# LD_driver.net
KiCad netlist of a schematic drawn in Altium Designer
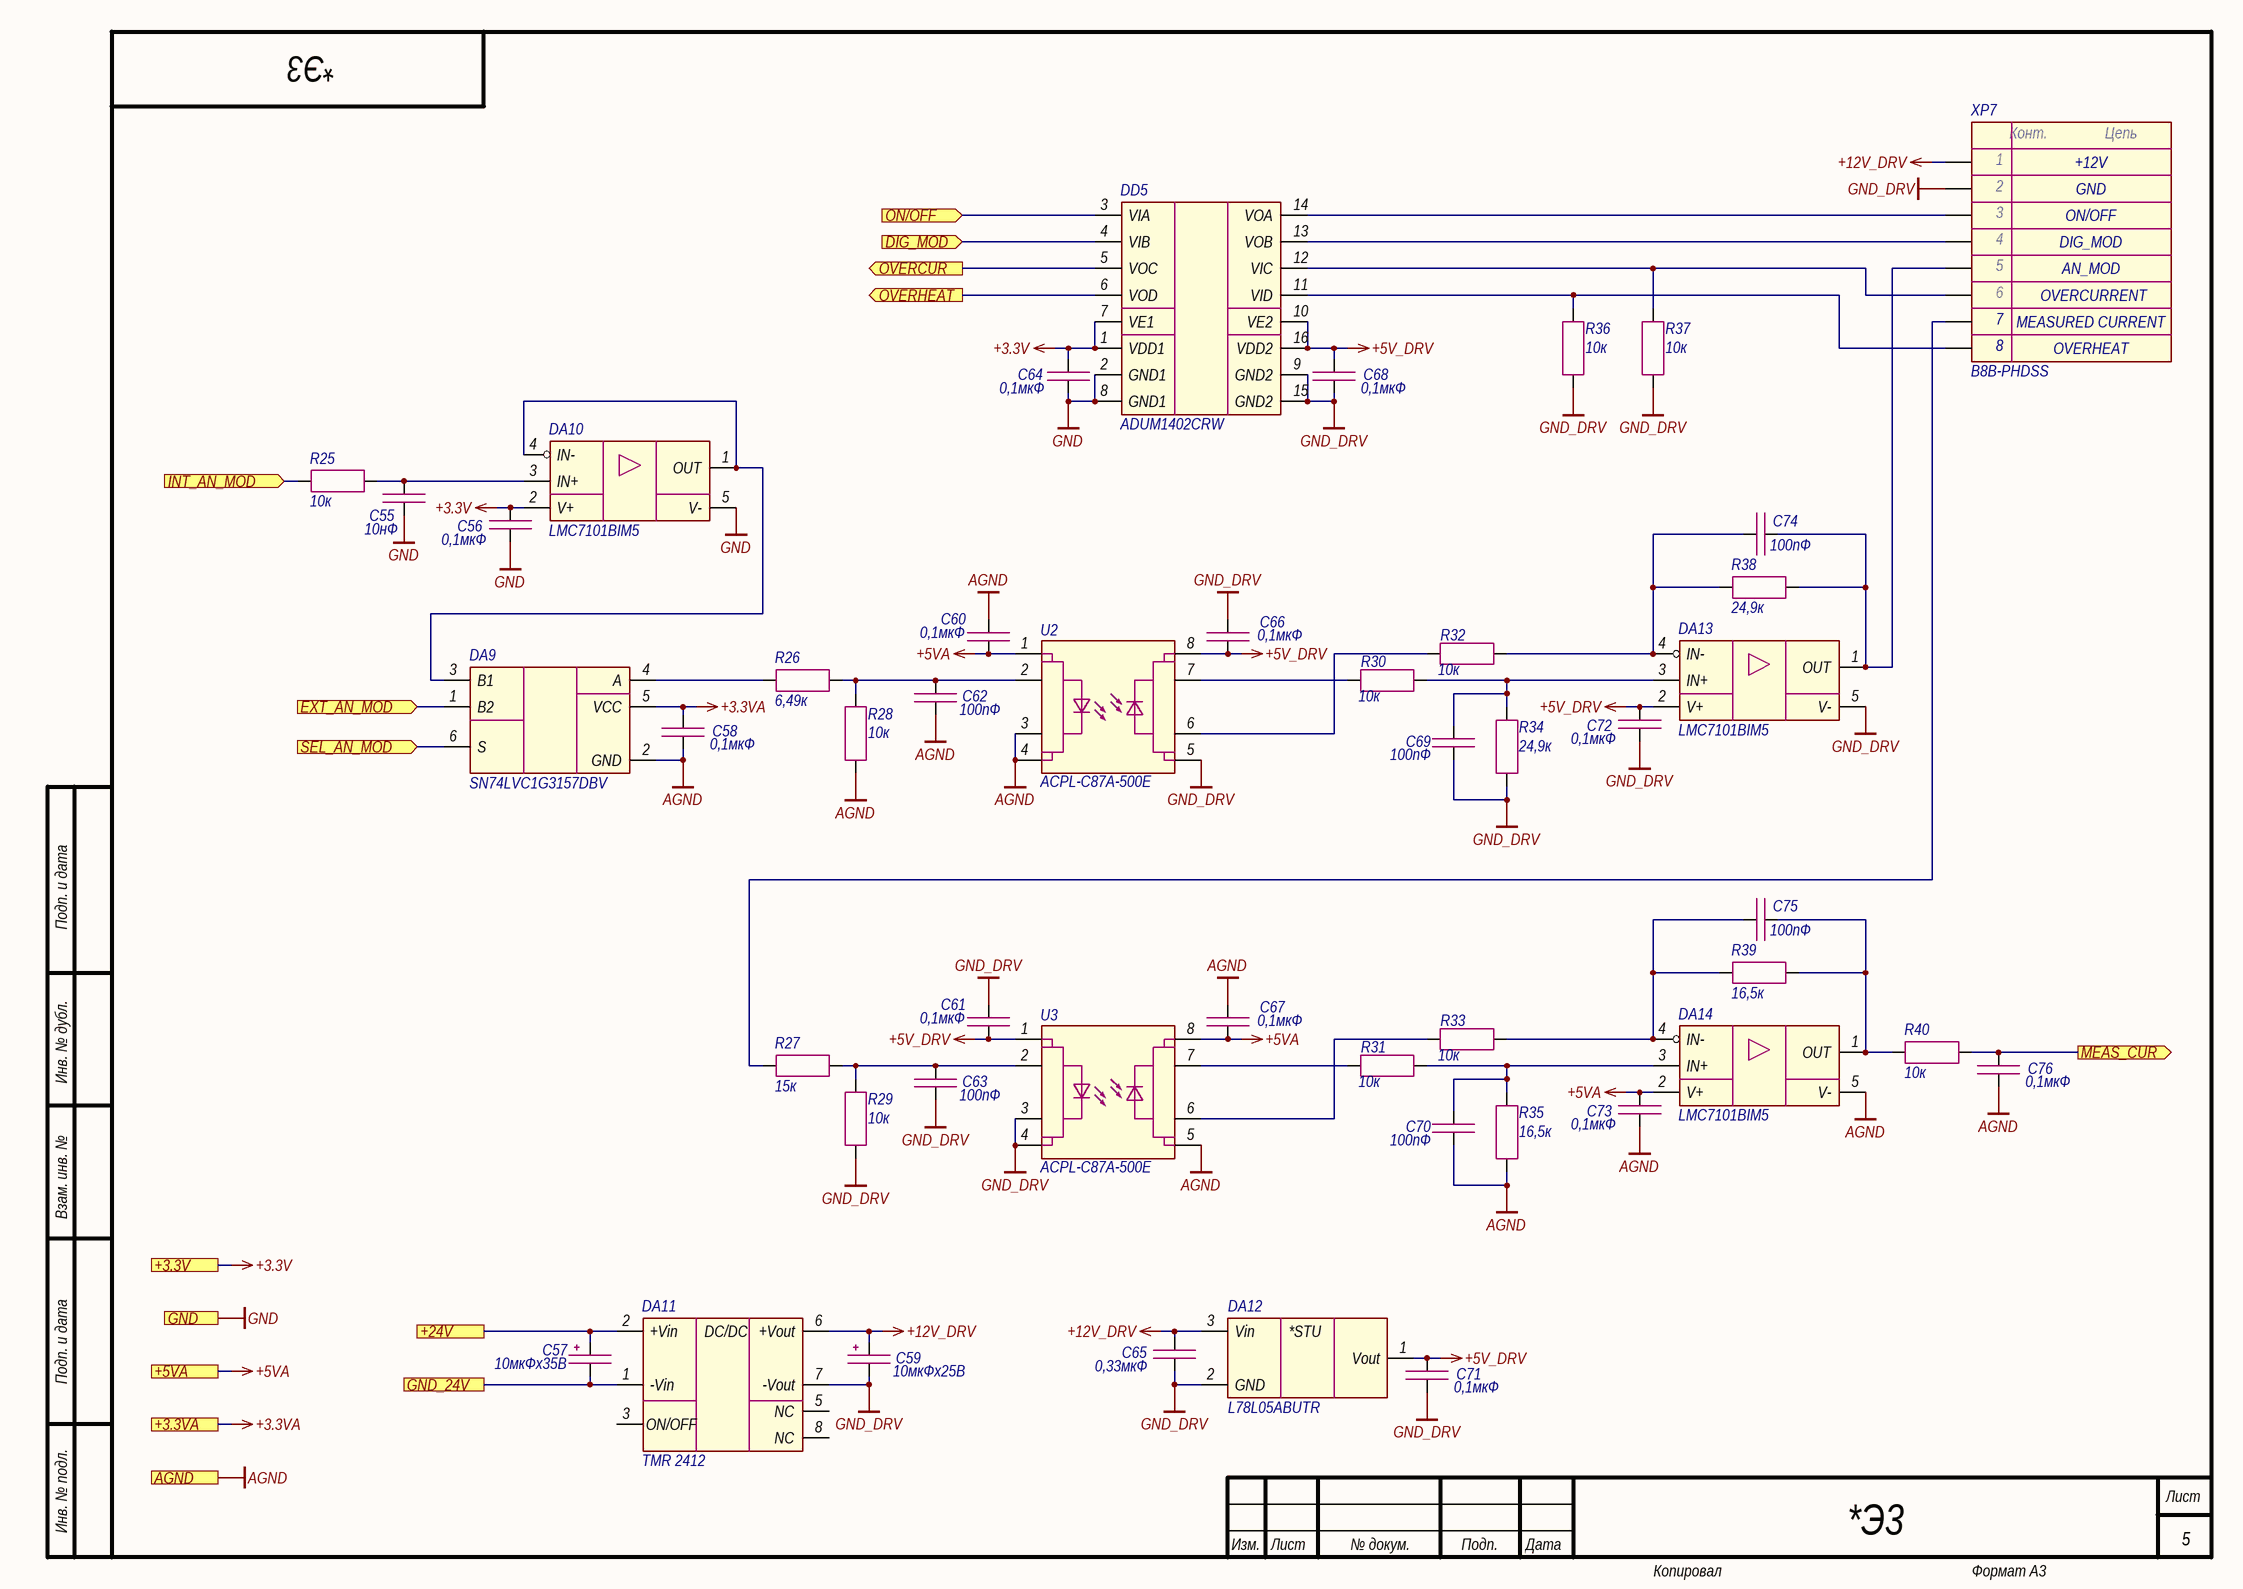
[diagram p0: LD_driver.SchDoc]

(export (version "E")
  (design (tool "Eeschema 10.0.6"))
  (components
    (comp (ref "C55")
      (value "10нФ")
      (footprint "Pcb_library:CAP_0603")
      (fields (field (name "MANUFACTURER") "Murata"))
      (libsource (lib "Schem_library") (part "Capacitor"))
    )
    (comp (ref "C56")
      (value "0,1мкФ")
      (footprint "Pcb_library:CAP_0603")
      (fields (field (name "MANUFACTURER") "Murata"))
      (libsource (lib "Schem_library") (part "Capacitor"))
    )
    (comp (ref "C57")
      (value "10мкФх35B")
      (footprint "Pcb_library:CAP_C")
      (libsource (lib "Schem_library") (part "Capacitor_Polar"))
    )
    (comp (ref "C58")
      (value "0,1мкФ")
      (footprint "Pcb_library:CAP_0603")
      (fields (field (name "MANUFACTURER") "Murata"))
      (libsource (lib "Schem_library") (part "Capacitor"))
    )
    (comp (ref "C59")
      (value "10мкФх25B")
      (footprint "Pcb_library:CAP_B")
      (libsource (lib "Schem_library") (part "Capacitor_Polar"))
    )
    (comp (ref "C60")
      (value "0,1мкФ")
      (footprint "Pcb_library:CAP_0603")
      (fields (field (name "MANUFACTURER") "Murata"))
      (libsource (lib "Schem_library") (part "Capacitor"))
    )
    (comp (ref "C61")
      (value "0,1мкФ")
      (footprint "Pcb_library:CAP_0603")
      (fields (field (name "MANUFACTURER") "Murata"))
      (libsource (lib "Schem_library") (part "Capacitor"))
    )
    (comp (ref "C62")
      (value "100пФ")
      (footprint "Pcb_library:CAP_0603")
      (fields (field (name "MANUFACTURER") "Murata"))
      (libsource (lib "Schem_library") (part "Capacitor"))
    )
    (comp (ref "C63")
      (value "100пФ")
      (footprint "Pcb_library:CAP_0603")
      (fields (field (name "MANUFACTURER") "Murata"))
      (libsource (lib "Schem_library") (part "Capacitor"))
    )
    (comp (ref "C64")
      (value "0,1мкФ")
      (footprint "Pcb_library:CAP_0603")
      (fields (field (name "MANUFACTURER") "Murata"))
      (libsource (lib "Schem_library") (part "Capacitor"))
    )
    (comp (ref "C65")
      (value "0,33мкФ")
      (footprint "Pcb_library:CAP_0805")
      (fields (field (name "MANUFACTURER") "Murata"))
      (libsource (lib "Schem_library") (part "Capacitor"))
    )
    (comp (ref "C66")
      (value "0,1мкФ")
      (footprint "Pcb_library:CAP_0603")
      (fields (field (name "MANUFACTURER") "Murata"))
      (libsource (lib "Schem_library") (part "Capacitor"))
    )
    (comp (ref "C67")
      (value "0,1мкФ")
      (footprint "Pcb_library:CAP_0603")
      (fields (field (name "MANUFACTURER") "Murata"))
      (libsource (lib "Schem_library") (part "Capacitor"))
    )
    (comp (ref "C68")
      (value "0,1мкФ")
      (footprint "Pcb_library:CAP_0603")
      (fields (field (name "MANUFACTURER") "Murata"))
      (libsource (lib "Schem_library") (part "Capacitor"))
    )
    (comp (ref "C69")
      (value "100пФ")
      (footprint "Pcb_library:CAP_0603")
      (fields (field (name "MANUFACTURER") "Murata"))
      (libsource (lib "Schem_library") (part "Capacitor"))
    )
    (comp (ref "C70")
      (value "100пФ")
      (footprint "Pcb_library:CAP_0603")
      (fields (field (name "MANUFACTURER") "Murata"))
      (libsource (lib "Schem_library") (part "Capacitor"))
    )
    (comp (ref "C71")
      (value "0,1мкФ")
      (footprint "Pcb_library:CAP_0603")
      (fields (field (name "MANUFACTURER") "Murata"))
      (libsource (lib "Schem_library") (part "Capacitor"))
    )
    (comp (ref "C72")
      (value "0,1мкФ")
      (footprint "Pcb_library:CAP_0603")
      (fields (field (name "MANUFACTURER") "Murata"))
      (libsource (lib "Schem_library") (part "Capacitor"))
    )
    (comp (ref "C73")
      (value "0,1мкФ")
      (footprint "Pcb_library:CAP_0603")
      (fields (field (name "MANUFACTURER") "Murata"))
      (libsource (lib "Schem_library") (part "Capacitor"))
    )
    (comp (ref "C74")
      (value "100пФ")
      (footprint "Pcb_library:CAP_0603")
      (fields (field (name "MANUFACTURER") "Murata"))
      (libsource (lib "Schem_library") (part "Capacitor"))
    )
    (comp (ref "C75")
      (value "100пФ")
      (footprint "Pcb_library:CAP_0603")
      (fields (field (name "MANUFACTURER") "Murata"))
      (libsource (lib "Schem_library") (part "Capacitor"))
    )
    (comp (ref "C76")
      (value "0,1мкФ")
      (footprint "Pcb_library:CAP_0603")
      (fields (field (name "MANUFACTURER") "Murata"))
      (libsource (lib "Schem_library") (part "Capacitor"))
    )
    (comp (ref "DA9")
      (value "SN74LVC1G3157DBV")
      (footprint "Pcb_library:SOT-23-6")
      (fields (field (name "MANUFACTURER") "Texas Instruments"))
      (libsource (lib "Schem_library") (part "SN74LVC1G3157"))
    )
    (comp (ref "DA10")
      (value "LMC7101BIM5")
      (footprint "Pcb_library:SOT-23-5")
      (fields (field (name "MANUFACTURER") "Texas Instruments"))
      (libsource (lib "Schem_library") (part "LMC7101"))
    )
    (comp (ref "DA11")
      (value "TMR 2412")
      (footprint "Pcb_library:TMR3 (SIP-8)")
      (fields (field (name "MANUFACTURER") "Traco Power"))
      (libsource (lib "Schem_library") (part "TMR3"))
    )
    (comp (ref "DA12")
      (value "L78L05ABUTR")
      (footprint "Pcb_library:SOT-89")
      (fields (field (name "MANUFACTURER") "STMicroelectronics"))
      (libsource (lib "Schem_library") (part "LD2981ABU50TR"))
    )
    (comp (ref "DA13")
      (value "LMC7101BIM5")
      (footprint "Pcb_library:SOT-23-5")
      (fields (field (name "MANUFACTURER") "Texas Instruments"))
      (libsource (lib "Schem_library") (part "LMC7101"))
    )
    (comp (ref "DA14")
      (value "LMC7101BIM5")
      (footprint "Pcb_library:SOT-23-5")
      (fields (field (name "MANUFACTURER") "Texas Instruments"))
      (libsource (lib "Schem_library") (part "LMC7101"))
    )
    (comp (ref "DD5")
      (value "ADUM1402CRW")
      (footprint "Pcb_library:SOIC-16W")
      (fields (field (name "MANUFACTURER") "Analog Devices"))
      (libsource (lib "Schem_library") (part "ADUM1402"))
    )
    (comp (ref "R25")
      (value "10к")
      (footprint "Pcb_library:RES_0603")
      (fields (field (name "MANUFACTURER") "Yageo"))
      (libsource (lib "Schem_library") (part "Resistor"))
    )
    (comp (ref "R26")
      (value "6,49к")
      (footprint "Pcb_library:RES_0603")
      (fields (field (name "MANUFACTURER") "Yageo"))
      (libsource (lib "Schem_library") (part "Resistor"))
    )
    (comp (ref "R27")
      (value "15к")
      (footprint "Pcb_library:RES_0603")
      (fields (field (name "MANUFACTURER") "Yageo"))
      (libsource (lib "Schem_library") (part "Resistor"))
    )
    (comp (ref "R28")
      (value "10к")
      (footprint "Pcb_library:RES_0603")
      (fields (field (name "MANUFACTURER") "Yageo"))
      (libsource (lib "Schem_library") (part "Resistor"))
    )
    (comp (ref "R29")
      (value "10к")
      (footprint "Pcb_library:RES_0603")
      (fields (field (name "MANUFACTURER") "Yageo"))
      (libsource (lib "Schem_library") (part "Resistor"))
    )
    (comp (ref "R30")
      (value "10к")
      (footprint "Pcb_library:RES_0603")
      (fields (field (name "MANUFACTURER") "Yageo"))
      (libsource (lib "Schem_library") (part "Resistor"))
    )
    (comp (ref "R31")
      (value "10к")
      (footprint "Pcb_library:RES_0603")
      (fields (field (name "MANUFACTURER") "Yageo"))
      (libsource (lib "Schem_library") (part "Resistor"))
    )
    (comp (ref "R32")
      (value "10к")
      (footprint "Pcb_library:RES_0603")
      (fields (field (name "MANUFACTURER") "Yageo"))
      (libsource (lib "Schem_library") (part "Resistor"))
    )
    (comp (ref "R33")
      (value "10к")
      (footprint "Pcb_library:RES_0603")
      (fields (field (name "MANUFACTURER") "Yageo"))
      (libsource (lib "Schem_library") (part "Resistor"))
    )
    (comp (ref "R34")
      (value "24,9к")
      (footprint "Pcb_library:RES_0603")
      (fields (field (name "MANUFACTURER") "Yageo"))
      (libsource (lib "Schem_library") (part "Resistor"))
    )
    (comp (ref "R35")
      (value "16,5к")
      (footprint "Pcb_library:RES_0603")
      (fields (field (name "MANUFACTURER") "Yageo"))
      (libsource (lib "Schem_library") (part "Resistor"))
    )
    (comp (ref "R36")
      (value "10к")
      (footprint "Pcb_library:RES_0603")
      (fields (field (name "MANUFACTURER") "Yageo"))
      (libsource (lib "Schem_library") (part "Resistor"))
    )
    (comp (ref "R37")
      (value "10к")
      (footprint "Pcb_library:RES_0603")
      (fields (field (name "MANUFACTURER") "Yageo"))
      (libsource (lib "Schem_library") (part "Resistor"))
    )
    (comp (ref "R38")
      (value "24,9к")
      (footprint "Pcb_library:RES_0603")
      (fields (field (name "MANUFACTURER") "Yageo"))
      (libsource (lib "Schem_library") (part "Resistor"))
    )
    (comp (ref "R39")
      (value "16,5к")
      (footprint "Pcb_library:RES_0603")
      (fields (field (name "MANUFACTURER") "Yageo"))
      (libsource (lib "Schem_library") (part "Resistor"))
    )
    (comp (ref "R40")
      (value "10к")
      (footprint "Pcb_library:RES_0603")
      (fields (field (name "MANUFACTURER") "Yageo"))
      (libsource (lib "Schem_library") (part "Resistor"))
    )
    (comp (ref "U2")
      (value "ACPL-C87A-500E")
      (footprint "Pcb_library:SSO-8")
      (fields (field (name "MANUFACTURER") "Broadcom"))
      (libsource (lib "Schem_library") (part "ACPL-C87"))
    )
    (comp (ref "U3")
      (value "ACPL-C87A-500E")
      (footprint "Pcb_library:SSO-8")
      (fields (field (name "MANUFACTURER") "Broadcom"))
      (libsource (lib "Schem_library") (part "ACPL-C87"))
    )
    (comp (ref "XP7")
      (value "B8B-PHDSS")
      (footprint "Pcb_library:B8B-PHDSS")
      (fields (field (name "MANUFACTURER") "JST"))
      (libsource (lib "Schem_library") (part "Connector-8"))
    )
  )
  (nets
    (net (code "1") (name "+3.3V") (class "Default")
      (node (ref "C56") (pin "1") (pinfunction "1_1") (pintype "passive"))
      (node (ref "C64") (pin "1") (pinfunction "1_1") (pintype "passive"))
      (node (ref "DA10") (pin "2") (pinfunction "V+_2") (pintype "passive"))
      (node (ref "DD5") (pin "1") (pinfunction "VDD1_1") (pintype "passive"))
      (node (ref "DD5") (pin "7") (pinfunction "VE1_7") (pintype "passive"))
    )
    (net (code "2") (name "+3.3VA") (class "Default")
      (node (ref "C58") (pin "1") (pinfunction "1_1") (pintype "passive"))
      (node (ref "DA9") (pin "5") (pinfunction "VCC_5") (pintype "passive"))
    )
    (net (code "3") (name "+5VA") (class "Default")
      (node (ref "C60") (pin "1") (pinfunction "1_1") (pintype "passive"))
      (node (ref "C67") (pin "1") (pinfunction "1_1") (pintype "passive"))
      (node (ref "C73") (pin "1") (pinfunction "1_1") (pintype "passive"))
      (node (ref "DA14") (pin "2") (pinfunction "V+_2") (pintype "passive"))
      (node (ref "U2") (pin "1") (pinfunction "VDD1_1") (pintype "passive"))
      (node (ref "U3") (pin "8") (pinfunction "VDD2_8") (pintype "passive"))
    )
    (net (code "4") (name "+5V_DRV") (class "Default")
      (node (ref "C61") (pin "1") (pinfunction "1_1") (pintype "passive"))
      (node (ref "C66") (pin "1") (pinfunction "1_1") (pintype "passive"))
      (node (ref "C68") (pin "1") (pinfunction "1_1") (pintype "passive"))
      (node (ref "C71") (pin "1") (pinfunction "1_1") (pintype "passive"))
      (node (ref "C72") (pin "1") (pinfunction "1_1") (pintype "passive"))
      (node (ref "DA12") (pin "1") (pinfunction "Vout_1") (pintype "passive"))
      (node (ref "DA13") (pin "2") (pinfunction "V+_2") (pintype "passive"))
      (node (ref "DD5") (pin "10") (pinfunction "VE2_10") (pintype "passive"))
      (node (ref "DD5") (pin "16") (pinfunction "VDD2_16") (pintype "passive"))
      (node (ref "U2") (pin "8") (pinfunction "VDD2_8") (pintype "passive"))
      (node (ref "U3") (pin "1") (pinfunction "VDD1_1") (pintype "passive"))
    )
    (net (code "5") (name "+12V_DRV") (class "Default")
      (node (ref "C59") (pin "1") (pinfunction "1_1") (pintype "passive"))
      (node (ref "C65") (pin "2") (pinfunction "2_2") (pintype "passive"))
      (node (ref "DA11") (pin "6") (pinfunction "+Vout_6") (pintype "passive"))
      (node (ref "DA12") (pin "3") (pinfunction "Vin_3") (pintype "passive"))
      (node (ref "XP7") (pin "1") (pintype "passive"))
    )
    (net (code "6") (name "/+24V") (class "Default")
      (node (ref "C57") (pin "1") (pinfunction "1_1") (pintype "passive"))
      (node (ref "DA11") (pin "2") (pinfunction "+Vin_2") (pintype "passive"))
    )
    (net (code "7") (name "/DIG_MOD") (class "Default")
      (node (ref "DD5") (pin "4") (pinfunction "VIB_4") (pintype "passive"))
    )
    (net (code "8") (name "/EXT_AN_MOD") (class "Default")
      (node (ref "DA9") (pin "1") (pinfunction "B2_1") (pintype "passive"))
    )
    (net (code "9") (name "/GND_24V") (class "Default")
      (node (ref "C57") (pin "2") (pinfunction "2_2") (pintype "passive"))
      (node (ref "DA11") (pin "1") (pinfunction "-Vin_1") (pintype "passive"))
    )
    (net (code "10") (name "/INT_AN_MOD") (class "Default")
      (node (ref "R25") (pin "1") (pinfunction "1_1") (pintype "passive"))
    )
    (net (code "11") (name "/MEAS_CUR") (class "Default")
      (node (ref "C76") (pin "1") (pinfunction "1_1") (pintype "passive"))
      (node (ref "R40") (pin "2") (pinfunction "2_2") (pintype "passive"))
    )
    (net (code "12") (name "/ON{slash}OFF") (class "Default")
      (node (ref "DD5") (pin "3") (pinfunction "VIA_3") (pintype "passive"))
    )
    (net (code "13") (name "/OVERCUR") (class "Default")
      (node (ref "DD5") (pin "5") (pinfunction "VOC_5") (pintype "passive"))
    )
    (net (code "14") (name "/OVERHEAT") (class "Default")
      (node (ref "DD5") (pin "6") (pinfunction "VOD_6") (pintype "passive"))
    )
    (net (code "15") (name "/SEL_AN_MOD") (class "Default")
      (node (ref "DA9") (pin "6") (pinfunction "S_6") (pintype "passive"))
    )
    (net (code "16") (name "AGND") (class "Default")
      (node (ref "C58") (pin "2") (pinfunction "2_2") (pintype "passive"))
      (node (ref "C60") (pin "2") (pinfunction "2_2") (pintype "passive"))
      (node (ref "C62") (pin "1") (pinfunction "1_1") (pintype "passive"))
      (node (ref "C67") (pin "2") (pinfunction "2_2") (pintype "passive"))
      (node (ref "C70") (pin "2") (pinfunction "2_2") (pintype "passive"))
      (node (ref "C73") (pin "2") (pinfunction "2_2") (pintype "passive"))
      (node (ref "C76") (pin "2") (pinfunction "2_2") (pintype "passive"))
      (node (ref "DA14") (pin "5") (pinfunction "V-_5") (pintype "passive"))
      (node (ref "DA9") (pin "2") (pinfunction "GND_2") (pintype "passive"))
      (node (ref "R28") (pin "2") (pinfunction "2_2") (pintype "passive"))
      (node (ref "R35") (pin "2") (pinfunction "2_2") (pintype "passive"))
      (node (ref "U2") (pin "3") (pinfunction "SHDN_3") (pintype "passive"))
      (node (ref "U2") (pin "4") (pinfunction "GND1_4") (pintype "passive"))
      (node (ref "U3") (pin "5") (pinfunction "GND2_5") (pintype "passive"))
    )
    (net (code "17") (name "GND") (class "Default")
      (node (ref "C55") (pin "2") (pinfunction "2_2") (pintype "passive"))
      (node (ref "C56") (pin "2") (pinfunction "2_2") (pintype "passive"))
      (node (ref "C64") (pin "2") (pinfunction "2_2") (pintype "passive"))
      (node (ref "DA10") (pin "5") (pinfunction "V-_5") (pintype "passive"))
      (node (ref "DD5") (pin "2") (pinfunction "GND1_2") (pintype "passive"))
      (node (ref "DD5") (pin "8") (pinfunction "GND1_8") (pintype "passive"))
    )
    (net (code "18") (name "GND_DRV") (class "Default")
      (node (ref "C59") (pin "2") (pinfunction "2_2") (pintype "passive"))
      (node (ref "C61") (pin "2") (pinfunction "2_2") (pintype "passive"))
      (node (ref "C63") (pin "1") (pinfunction "1_1") (pintype "passive"))
      (node (ref "C65") (pin "1") (pinfunction "1_1") (pintype "passive"))
      (node (ref "C66") (pin "2") (pinfunction "2_2") (pintype "passive"))
      (node (ref "C68") (pin "2") (pinfunction "2_2") (pintype "passive"))
      (node (ref "C69") (pin "2") (pinfunction "2_2") (pintype "passive"))
      (node (ref "C71") (pin "2") (pinfunction "2_2") (pintype "passive"))
      (node (ref "C72") (pin "2") (pinfunction "2_2") (pintype "passive"))
      (node (ref "DA11") (pin "7") (pinfunction "-Vout_7") (pintype "passive"))
      (node (ref "DA12") (pin "2") (pinfunction "GND_2") (pintype "passive"))
      (node (ref "DA13") (pin "5") (pinfunction "V-_5") (pintype "passive"))
      (node (ref "DD5") (pin "15") (pinfunction "GND2_15") (pintype "passive"))
      (node (ref "DD5") (pin "9") (pinfunction "GND2_9") (pintype "passive"))
      (node (ref "R29") (pin "2") (pinfunction "2_2") (pintype "passive"))
      (node (ref "R34") (pin "1") (pinfunction "1_1") (pintype "passive"))
      (node (ref "R36") (pin "2") (pinfunction "2_2") (pintype "passive"))
      (node (ref "R37") (pin "2") (pinfunction "2_2") (pintype "passive"))
      (node (ref "U2") (pin "5") (pinfunction "GND2_5") (pintype "passive"))
      (node (ref "U3") (pin "3") (pinfunction "SHDN_3") (pintype "passive"))
      (node (ref "U3") (pin "4") (pinfunction "GND1_4") (pintype "passive"))
      (node (ref "XP7") (pin "2") (pintype "passive"))
    )
    (net (code "19") (name "Net-(DA9-A)") (class "Default")
      (node (ref "DA9") (pin "4") (pinfunction "A_4") (pintype "passive"))
      (node (ref "R26") (pin "2") (pinfunction "2_2") (pintype "passive"))
    )
    (net (code "20") (name "Net-(DA10-IN+)") (class "Default")
      (node (ref "C55") (pin "1") (pinfunction "1_1") (pintype "passive"))
      (node (ref "DA10") (pin "3") (pinfunction "IN+_3") (pintype "passive"))
      (node (ref "R25") (pin "2") (pinfunction "2_2") (pintype "passive"))
    )
    (net (code "21") (name "Net-(DA10-IN-)") (class "Default")
      (node (ref "DA10") (pin "1") (pinfunction "OUT_1") (pintype "passive"))
      (node (ref "DA10") (pin "4") (pinfunction "IN-_4") (pintype "passive"))
      (node (ref "DA9") (pin "3") (pinfunction "B1_3") (pintype "passive"))
    )
    (net (code "22") (name "Net-(DA13-IN+)") (class "Default")
      (node (ref "C69") (pin "1") (pinfunction "1_1") (pintype "passive"))
      (node (ref "DA13") (pin "3") (pinfunction "IN+_3") (pintype "passive"))
      (node (ref "R30") (pin "2") (pinfunction "2_2") (pintype "passive"))
      (node (ref "R34") (pin "2") (pinfunction "2_2") (pintype "passive"))
    )
    (net (code "23") (name "Net-(DA13-IN-)") (class "Default")
      (node (ref "C74") (pin "1") (pinfunction "1_1") (pintype "passive"))
      (node (ref "DA13") (pin "4") (pinfunction "IN-_4") (pintype "passive"))
      (node (ref "R32") (pin "2") (pinfunction "2_2") (pintype "passive"))
      (node (ref "R38") (pin "1") (pinfunction "1_1") (pintype "passive"))
    )
    (net (code "24") (name "Net-(DA13-OUT)") (class "Default")
      (node (ref "C74") (pin "2") (pinfunction "2_2") (pintype "passive"))
      (node (ref "DA13") (pin "1") (pinfunction "OUT_1") (pintype "passive"))
      (node (ref "R38") (pin "2") (pinfunction "2_2") (pintype "passive"))
      (node (ref "XP7") (pin "5") (pintype "passive"))
    )
    (net (code "25") (name "Net-(DA14-IN+)") (class "Default")
      (node (ref "C70") (pin "1") (pinfunction "1_1") (pintype "passive"))
      (node (ref "DA14") (pin "3") (pinfunction "IN+_3") (pintype "passive"))
      (node (ref "R31") (pin "2") (pinfunction "2_2") (pintype "passive"))
      (node (ref "R35") (pin "1") (pinfunction "1_1") (pintype "passive"))
    )
    (net (code "26") (name "Net-(DA14-IN-)") (class "Default")
      (node (ref "C75") (pin "1") (pinfunction "1_1") (pintype "passive"))
      (node (ref "DA14") (pin "4") (pinfunction "IN-_4") (pintype "passive"))
      (node (ref "R33") (pin "2") (pinfunction "2_2") (pintype "passive"))
      (node (ref "R39") (pin "2") (pinfunction "2_2") (pintype "passive"))
    )
    (net (code "27") (name "Net-(DA14-OUT)") (class "Default")
      (node (ref "C75") (pin "2") (pinfunction "2_2") (pintype "passive"))
      (node (ref "DA14") (pin "1") (pinfunction "OUT_1") (pintype "passive"))
      (node (ref "R39") (pin "1") (pinfunction "1_1") (pintype "passive"))
      (node (ref "R40") (pin "1") (pinfunction "1_1") (pintype "passive"))
    )
    (net (code "28") (name "Net-(DD5-VIC)") (class "Default")
      (node (ref "DD5") (pin "12") (pinfunction "VIC_12") (pintype "passive"))
      (node (ref "R37") (pin "1") (pinfunction "1_1") (pintype "passive"))
      (node (ref "XP7") (pin "6") (pintype "passive"))
    )
    (net (code "29") (name "Net-(DD5-VID)") (class "Default")
      (node (ref "DD5") (pin "11") (pinfunction "VID_11") (pintype "passive"))
      (node (ref "R36") (pin "1") (pinfunction "1_1") (pintype "passive"))
      (node (ref "XP7") (pin "8") (pintype "passive"))
    )
    (net (code "30") (name "Net-(DD5-VOA)") (class "Default")
      (node (ref "DD5") (pin "14") (pinfunction "VOA_14") (pintype "passive"))
      (node (ref "XP7") (pin "3") (pintype "passive"))
    )
    (net (code "31") (name "Net-(DD5-VOB)") (class "Default")
      (node (ref "DD5") (pin "13") (pinfunction "VOB_13") (pintype "passive"))
      (node (ref "XP7") (pin "4") (pintype "passive"))
    )
    (net (code "32") (name "Net-(R27-Pad2)") (class "Default")
      (node (ref "R27") (pin "2") (pinfunction "2_2") (pintype "passive"))
      (node (ref "XP7") (pin "7") (pintype "passive"))
    )
    (net (code "33") (name "Net-(U2-VIN)") (class "Default")
      (node (ref "C62") (pin "2") (pinfunction "2_2") (pintype "passive"))
      (node (ref "R26") (pin "1") (pinfunction "1_1") (pintype "passive"))
      (node (ref "R28") (pin "1") (pinfunction "1_1") (pintype "passive"))
      (node (ref "U2") (pin "2") (pinfunction "VIN_2") (pintype "passive"))
    )
    (net (code "34") (name "Net-(U2-VOUT+)") (class "Default")
      (node (ref "R30") (pin "1") (pinfunction "1_1") (pintype "passive"))
      (node (ref "U2") (pin "7") (pinfunction "VOUT+_7") (pintype "passive"))
    )
    (net (code "35") (name "Net-(U2-VOUT-)") (class "Default")
      (node (ref "R32") (pin "1") (pinfunction "1_1") (pintype "passive"))
      (node (ref "U2") (pin "6") (pinfunction "VOUT-_6") (pintype "passive"))
    )
    (net (code "36") (name "Net-(U3-VIN)") (class "Default")
      (node (ref "C63") (pin "2") (pinfunction "2_2") (pintype "passive"))
      (node (ref "R27") (pin "1") (pinfunction "1_1") (pintype "passive"))
      (node (ref "R29") (pin "1") (pinfunction "1_1") (pintype "passive"))
      (node (ref "U3") (pin "2") (pinfunction "VIN_2") (pintype "passive"))
    )
    (net (code "37") (name "Net-(U3-VOUT+)") (class "Default")
      (node (ref "R31") (pin "1") (pinfunction "1_1") (pintype "passive"))
      (node (ref "U3") (pin "7") (pinfunction "VOUT+_7") (pintype "passive"))
    )
    (net (code "38") (name "Net-(U3-VOUT-)") (class "Default")
      (node (ref "R33") (pin "1") (pinfunction "1_1") (pintype "passive"))
      (node (ref "U3") (pin "6") (pinfunction "VOUT-_6") (pintype "passive"))
    )
    (net (code "39") (name "unconnected-(DA11-NC-Pad5)") (class "Default")
      (node (ref "DA11") (pin "5") (pinfunction "NC_5") (pintype "passive"))
    )
    (net (code "40") (name "unconnected-(DA11-NC-Pad8)") (class "Default")
      (node (ref "DA11") (pin "8") (pinfunction "NC_8") (pintype "passive"))
    )
    (net (code "41") (name "unconnected-(DA11-ON{slash}OFF-Pad3)") (class "Default")
      (node (ref "DA11") (pin "3") (pinfunction "ON/OFF_3") (pintype "passive"))
    )
  )
)
